# LNA.net
KiCad netlist of a schematic drawn in Altium Designer
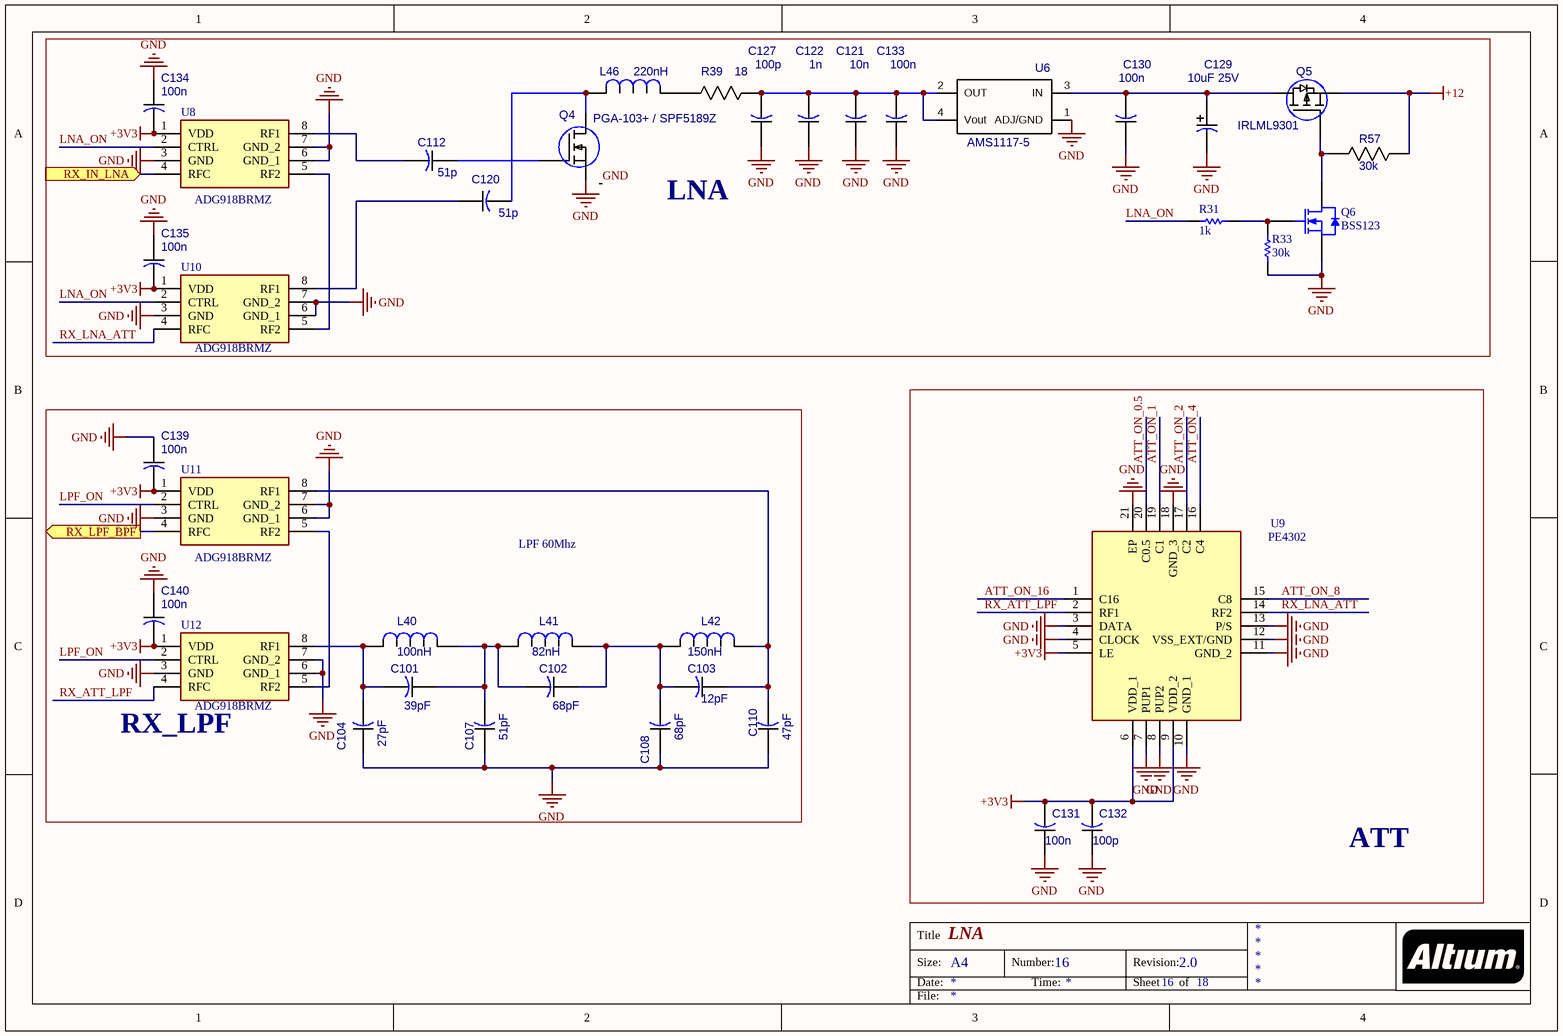
[diagram p0: LNA.SchDoc]

(export (version "E")
  (design (tool "Eeschema 10.0.6"))
  (components
    (comp (ref "C101")
      (value "39pF")
      (footprint "CAP_0805")
      (description "CAP_0805")
      (libsource (lib "*") (part "CAP_0805"))
    )
    (comp (ref "C102")
      (value "68pF")
      (footprint "CAP_0805")
      (description "CAP_0805")
      (libsource (lib "*") (part "CAP_0805"))
    )
    (comp (ref "C103")
      (value "12pF")
      (footprint "CAP_0805")
      (description "CAP_0805")
      (libsource (lib "*") (part "CAP_0805"))
    )
    (comp (ref "C104")
      (value "27pF")
      (footprint "CAP_0805")
      (description "CAP_0805")
      (libsource (lib "*") (part "CAP_0805"))
    )
    (comp (ref "C107")
      (value "51pF")
      (footprint "CAP_0805")
      (description "CAP_0805")
      (libsource (lib "*") (part "CAP_0805"))
    )
    (comp (ref "C108")
      (value "68pF")
      (footprint "CAP_0805")
      (description "CAP_0805")
      (libsource (lib "*") (part "CAP_0805"))
    )
    (comp (ref "C110")
      (value "47pF")
      (footprint "CAP_0805")
      (description "CAP_0805")
      (libsource (lib "*") (part "CAP_0805"))
    )
    (comp (ref "C112")
      (value "51p")
      (footprint "CAP_0805")
      (description "CAP_0805")
      (libsource (lib "*") (part "CAP_0805"))
    )
    (comp (ref "C120")
      (value "51p")
      (footprint "CAP_0805")
      (description "CAP_0805")
      (libsource (lib "*") (part "CAP_0805"))
    )
    (comp (ref "C121")
      (value "10n")
      (footprint "6-0805_M")
      (description "CAP_0805")
      (libsource (lib "*") (part "CAP_0805"))
    )
    (comp (ref "C122")
      (value "1n")
      (footprint "6-0805_M")
      (description "CAP_0805")
      (libsource (lib "*") (part "CAP_0805"))
    )
    (comp (ref "C127")
      (value "100p")
      (footprint "6-0805_M")
      (description "CAP_0805")
      (libsource (lib "*") (part "CAP_0805"))
    )
    (comp (ref "C129")
      (value "10uF 25V")
      (footprint "CAPAE_5.3x5.3h6.1")
      (description "CAPAE_5.3x5.3h6.1")
      (libsource (lib "*") (part "CAPAE_5.3x5.3h6.1"))
    )
    (comp (ref "C130")
      (value "100n")
      (footprint "CAP_0805")
      (description "CAP_0805")
      (libsource (lib "") (part "CAP_0805_1"))
    )
    (comp (ref "C131")
      (value "100n")
      (footprint "6-0805_M")
      (description "CAP_0805")
      (libsource (lib "*") (part "CAP_0805"))
    )
    (comp (ref "C132")
      (value "100p")
      (footprint "6-0805_M")
      (description "CAP_0805")
      (libsource (lib "*") (part "CAP_0805"))
    )
    (comp (ref "C133")
      (value "100n")
      (footprint "CAP_0805")
      (description "CAP_0805")
      (libsource (lib "*") (part "CAP_0805"))
    )
    (comp (ref "C134")
      (value "100n")
      (footprint "CAP_0805")
      (description "CAP_0805")
      (libsource (lib "*") (part "CAP_0805"))
    )
    (comp (ref "C135")
      (value "100n")
      (footprint "CAP_0805")
      (description "CAP_0805")
      (libsource (lib "*") (part "CAP_0805"))
    )
    (comp (ref "C139")
      (value "100n")
      (footprint "CAP_0805")
      (description "CAP_0805")
      (libsource (lib "*") (part "CAP_0805"))
    )
    (comp (ref "C140")
      (value "100n")
      (footprint "CAP_0805")
      (description "CAP_0805")
      (libsource (lib "*") (part "CAP_0805"))
    )
    (comp (ref "L40")
      (value "100nH")
      (footprint "IND_0805")
      (description "IND_0805")
      (libsource (lib "*") (part "IND_0805"))
    )
    (comp (ref "L41")
      (value "82nH")
      (footprint "IND_0805")
      (description "IND_0805")
      (libsource (lib "*") (part "IND_0805"))
    )
    (comp (ref "L42")
      (value "150nH")
      (footprint "IND_0805")
      (description "IND_0805")
      (libsource (lib "*") (part "IND_0805"))
    )
    (comp (ref "L46")
      (value "220nH")
      (footprint "IND_1206")
      (description "IND_1206")
      (libsource (lib "*") (part "IND_1206"))
    )
    (comp (ref "Q4")
      (value "PGA-103+ / SPF5189Z")
      (footprint "SOT89")
      (libsource (lib "*") (part "PGA-103+"))
    )
    (comp (ref "Q5")
      (value "IRLML9301")
      (footprint "SOT23")
      (description "MOSFET")
      (libsource (lib "*") (part "MOSFET_ENH_PD"))
    )
    (comp (ref "Q6")
      (value "BSS123")
      (footprint "FAIR-SOT23-3_V")
      (fields (field (name "MANUFACTURER") "Fairchild"))
      (libsource (lib "Altium Content Vault") (part "NEMOS-GSD-3"))
    )
    (comp (ref "R31")
      (value "1k")
      (footprint "RESC2013X60X40NL20T25")
      (description "RES_0805")
      (fields (field (name "MANUFACTURER") "Panasonic") (field (name "PART NUMBER") "ERA-6AEB303V"))
      (libsource (lib "Altium Content Vault") (part "RES"))
    )
    (comp (ref "R33")
      (value "30k")
      (footprint "RESC2013X60X40NL20T25")
      (description "RES_0805")
      (fields (field (name "MANUFACTURER") "Panasonic") (field (name "PART NUMBER") "ERA-6AEB303V"))
      (libsource (lib "Altium Content Vault") (part "RES"))
    )
    (comp (ref "R39")
      (value "18")
      (footprint "RES_1206")
      (description "RES_1206")
      (libsource (lib "*") (part "RES_1206"))
    )
    (comp (ref "R57")
      (value "30k")
      (footprint "RES_0805")
      (description "RES_0805")
      (libsource (lib "*") (part "RES_0805"))
    )
    (comp (ref "U6") (value "AMS1117-5") (footprint "AMS1117-5") (libsource (lib "*") (part "AMS1117-5")))
    (comp (ref "U8")
      (value "ADG918BRMZ")
      (footprint "SamacSys:SOP65P490X110-8N")
      (description "Integrated Circuit")
      (fields (field (name "MOUSER PART NUMBER") "584-ADG918BRMZ") (field (name "RS PART NUMBER") "4969212P"))
      (libsource (lib "*") (part "ADG918BRMZ"))
    )
    (comp (ref "U9")
      (value "PE4302")
      (footprint "SamacSys:QFN50P400X400X90-21N")
      (description "Integrated Circuit")
      (fields (field (name "MANUFACTURER_PART_NUMBER") "PE4312C-Z"))
      (libsource (lib "*") (part "PE4312C-Z"))
    )
    (comp (ref "U10")
      (value "ADG918BRMZ")
      (footprint "SamacSys:SOP65P490X110-8N")
      (description "Integrated Circuit")
      (fields (field (name "MOUSER PART NUMBER") "584-ADG918BRMZ") (field (name "RS PART NUMBER") "4969212P"))
      (libsource (lib "*") (part "ADG918BRMZ"))
    )
    (comp (ref "U11")
      (value "ADG918BRMZ")
      (footprint "SamacSys:SOP65P490X110-8N")
      (description "Integrated Circuit")
      (fields (field (name "MOUSER PART NUMBER") "584-ADG918BRMZ") (field (name "RS PART NUMBER") "4969212P"))
      (libsource (lib "*") (part "ADG918BRMZ"))
    )
    (comp (ref "U12")
      (value "ADG918BRMZ")
      (footprint "SamacSys:SOP65P490X110-8N")
      (description "Integrated Circuit")
      (fields (field (name "MOUSER PART NUMBER") "584-ADG918BRMZ") (field (name "RS PART NUMBER") "4969212P"))
      (libsource (lib "*") (part "ADG918BRMZ"))
    )
  )
  (nets
    (net (code "1") (name "+3V3") (class "Default")
      (node (ref "C131") (pin "2") (pinfunction "2_2") (pintype "passive"))
      (node (ref "C132") (pin "2") (pinfunction "2_2") (pintype "passive"))
      (node (ref "C134") (pin "2") (pinfunction "2_2") (pintype "passive"))
      (node (ref "C135") (pin "2") (pinfunction "2_2") (pintype "passive"))
      (node (ref "C139") (pin "2") (pinfunction "2_2") (pintype "passive"))
      (node (ref "C140") (pin "2") (pinfunction "2_2") (pintype "passive"))
      (node (ref "U10") (pin "1") (pinfunction "VDD_1") (pintype "power_in"))
      (node (ref "U11") (pin "1") (pinfunction "VDD_1") (pintype "power_in"))
      (node (ref "U12") (pin "1") (pinfunction "VDD_1") (pintype "power_in"))
      (node (ref "U8") (pin "1") (pinfunction "VDD_1") (pintype "power_in"))
      (node (ref "U9") (pin "5") (pinfunction "LE_5") (pintype "passive"))
      (node (ref "U9") (pin "6") (pinfunction "VDD_1_6") (pintype "passive"))
      (node (ref "U9") (pin "9") (pinfunction "VDD_2_9") (pintype "passive"))
    )
    (net (code "2") (name "+12") (class "Default")
      (node (ref "Q5") (pin "2") (pinfunction "S_2") (pintype "passive"))
      (node (ref "R57") (pin "2") (pinfunction "2_2") (pintype "passive"))
    )
    (net (code "3") (name "/ATT_ON_0.5") (class "Default")
      (node (ref "U9") (pin "20") (pinfunction "C0.5_20") (pintype "passive"))
    )
    (net (code "4") (name "/ATT_ON_1") (class "Default")
      (node (ref "U9") (pin "19") (pinfunction "C1_19") (pintype "passive"))
    )
    (net (code "5") (name "/ATT_ON_2") (class "Default")
      (node (ref "U9") (pin "17") (pinfunction "C2_17") (pintype "passive"))
    )
    (net (code "6") (name "/ATT_ON_4") (class "Default")
      (node (ref "U9") (pin "16") (pinfunction "C4_16") (pintype "passive"))
    )
    (net (code "7") (name "/ATT_ON_8") (class "Default")
      (node (ref "U9") (pin "15") (pinfunction "C8_15") (pintype "passive"))
    )
    (net (code "8") (name "/ATT_ON_16") (class "Default")
      (node (ref "U9") (pin "1") (pinfunction "C16_1") (pintype "passive"))
    )
    (net (code "9") (name "/LNA_ON") (class "Default")
      (node (ref "R31") (pin "2") (pinfunction "2_2") (pintype "passive"))
      (node (ref "U10") (pin "2") (pinfunction "CTRL_2") (pintype "passive"))
      (node (ref "U8") (pin "2") (pinfunction "CTRL_2") (pintype "passive"))
    )
    (net (code "10") (name "/LPF_ON") (class "Default")
      (node (ref "U11") (pin "2") (pinfunction "CTRL_2") (pintype "passive"))
      (node (ref "U12") (pin "2") (pinfunction "CTRL_2") (pintype "passive"))
    )
    (net (code "11") (name "/RX_ATT_LPF") (class "Default")
      (node (ref "U12") (pin "4") (pinfunction "RFC_4") (pintype "passive"))
      (node (ref "U9") (pin "2") (pinfunction "RF1_2") (pintype "passive"))
    )
    (net (code "12") (name "/RX_IN_LNA") (class "Default")
      (node (ref "U8") (pin "4") (pinfunction "RFC_4") (pintype "passive"))
    )
    (net (code "13") (name "/RX_LNA_ATT") (class "Default")
      (node (ref "U10") (pin "4") (pinfunction "RFC_4") (pintype "passive"))
      (node (ref "U9") (pin "14") (pinfunction "RF2_14") (pintype "passive"))
    )
    (net (code "14") (name "/RX_LPF_BPF") (class "Default")
      (node (ref "U11") (pin "4") (pinfunction "RFC_4") (pintype "passive"))
    )
    (net (code "15") (name "GND") (class "Default")
      (node (ref "C104") (pin "1") (pinfunction "1_1") (pintype "passive"))
      (node (ref "C107") (pin "1") (pinfunction "1_1") (pintype "passive"))
      (node (ref "C108") (pin "1") (pinfunction "1_1") (pintype "passive"))
      (node (ref "C110") (pin "1") (pinfunction "1_1") (pintype "passive"))
      (node (ref "C121") (pin "1") (pinfunction "1_1") (pintype "passive"))
      (node (ref "C122") (pin "1") (pinfunction "1_1") (pintype "passive"))
      (node (ref "C127") (pin "1") (pinfunction "1_1") (pintype "passive"))
      (node (ref "C129") (pin "2") (pinfunction "MINUS_2") (pintype "passive"))
      (node (ref "C130") (pin "1") (pinfunction "1_1") (pintype "passive"))
      (node (ref "C131") (pin "1") (pinfunction "1_1") (pintype "passive"))
      (node (ref "C132") (pin "1") (pinfunction "1_1") (pintype "passive"))
      (node (ref "C133") (pin "1") (pinfunction "1_1") (pintype "passive"))
      (node (ref "C134") (pin "1") (pinfunction "1_1") (pintype "passive"))
      (node (ref "C135") (pin "1") (pinfunction "1_1") (pintype "passive"))
      (node (ref "C139") (pin "1") (pinfunction "1_1") (pintype "passive"))
      (node (ref "C140") (pin "1") (pinfunction "1_1") (pintype "passive"))
      (node (ref "Q4") (pin "0") (pinfunction "0_0") (pintype "passive"))
      (node (ref "Q4") (pin "2") (pinfunction "S_2") (pintype "passive"))
      (node (ref "Q6") (pin "2") (pinfunction "S_2") (pintype "passive"))
      (node (ref "R33") (pin "1") (pinfunction "1_1") (pintype "passive"))
      (node (ref "U10") (pin "3") (pinfunction "GND_3") (pintype "power_in"))
      (node (ref "U10") (pin "6") (pinfunction "GND_1_6") (pintype "power_in"))
      (node (ref "U10") (pin "7") (pinfunction "GND_2_7") (pintype "power_in"))
      (node (ref "U11") (pin "3") (pinfunction "GND_3") (pintype "power_in"))
      (node (ref "U11") (pin "6") (pinfunction "GND_1_6") (pintype "power_in"))
      (node (ref "U11") (pin "7") (pinfunction "GND_2_7") (pintype "power_in"))
      (node (ref "U12") (pin "3") (pinfunction "GND_3") (pintype "power_in"))
      (node (ref "U12") (pin "6") (pinfunction "GND_1_6") (pintype "power_in"))
      (node (ref "U12") (pin "7") (pinfunction "GND_2_7") (pintype "power_in"))
      (node (ref "U6") (pin "1") (pinfunction "ADJ/GND_1") (pintype "passive"))
      (node (ref "U8") (pin "3") (pinfunction "GND_3") (pintype "power_in"))
      (node (ref "U8") (pin "6") (pinfunction "GND_1_6") (pintype "power_in"))
      (node (ref "U8") (pin "7") (pinfunction "GND_2_7") (pintype "power_in"))
      (node (ref "U9") (pin "10") (pinfunction "GND_1_10") (pintype "passive"))
      (node (ref "U9") (pin "11") (pinfunction "GND_2_11") (pintype "passive"))
      (node (ref "U9") (pin "12") (pinfunction "VSS_EXT/GND_12") (pintype "passive"))
      (node (ref "U9") (pin "13") (pinfunction "P/S_13") (pintype "passive"))
      (node (ref "U9") (pin "18") (pinfunction "GND_3_18") (pintype "passive"))
      (node (ref "U9") (pin "21") (pinfunction "EP_21") (pintype "passive"))
      (node (ref "U9") (pin "3") (pinfunction "DATA_3") (pintype "passive"))
      (node (ref "U9") (pin "4") (pinfunction "CLOCK_4") (pintype "passive"))
      (node (ref "U9") (pin "7") (pinfunction "PUP1_7") (pintype "passive"))
      (node (ref "U9") (pin "8") (pinfunction "PUP2_8") (pintype "passive"))
    )
    (net (code "16") (name "Net-(C101-Pad1)") (class "Default")
      (node (ref "C101") (pin "1") (pinfunction "1_1") (pintype "passive"))
      (node (ref "C102") (pin "2") (pinfunction "2_2") (pintype "passive"))
      (node (ref "C107") (pin "2") (pinfunction "2_2") (pintype "passive"))
      (node (ref "L40") (pin "2") (pinfunction "2_2") (pintype "passive"))
      (node (ref "L41") (pin "1") (pinfunction "1_1") (pintype "passive"))
    )
    (net (code "17") (name "Net-(C102-Pad1)") (class "Default")
      (node (ref "C102") (pin "1") (pinfunction "1_1") (pintype "passive"))
      (node (ref "C103") (pin "2") (pinfunction "2_2") (pintype "passive"))
      (node (ref "C108") (pin "2") (pinfunction "2_2") (pintype "passive"))
      (node (ref "L41") (pin "2") (pinfunction "2_2") (pintype "passive"))
      (node (ref "L42") (pin "1") (pinfunction "1_1") (pintype "passive"))
    )
    (net (code "18") (name "Net-(C129-PLUS)") (class "Default")
      (node (ref "C129") (pin "1") (pinfunction "PLUS_1") (pintype "passive"))
      (node (ref "C130") (pin "2") (pinfunction "2_2") (pintype "passive"))
      (node (ref "Q5") (pin "3") (pinfunction "D_3") (pintype "passive"))
      (node (ref "U6") (pin "3") (pinfunction "IN_3") (pintype "passive"))
    )
    (net (code "19") (name "Net-(L46-1)") (class "Default")
      (node (ref "C120") (pin "2") (pinfunction "2_2") (pintype "passive"))
      (node (ref "L46") (pin "2") (pinfunction "1_2") (pintype "passive"))
      (node (ref "Q4") (pin "3") (pinfunction "D_3") (pintype "passive"))
    )
    (net (code "20") (name "Net-(L46-2)") (class "Default")
      (node (ref "L46") (pin "1") (pinfunction "2_1") (pintype "passive"))
      (node (ref "R39") (pin "2") (pinfunction "2_2") (pintype "passive"))
    )
    (net (code "21") (name "Net-(Q4-G)") (class "Default")
      (node (ref "C112") (pin "1") (pinfunction "1_1") (pintype "passive"))
      (node (ref "Q4") (pin "1") (pinfunction "G_1") (pintype "passive"))
    )
    (net (code "22") (name "Net-(Q5-G)") (class "Default")
      (node (ref "Q5") (pin "1") (pinfunction "G_1") (pintype "passive"))
      (node (ref "Q6") (pin "3") (pinfunction "D_3") (pintype "passive"))
      (node (ref "R57") (pin "1") (pinfunction "1_1") (pintype "passive"))
    )
    (net (code "23") (name "Net-(Q6-G)") (class "Default")
      (node (ref "Q6") (pin "1") (pinfunction "G_1") (pintype "passive"))
      (node (ref "R31") (pin "1") (pinfunction "1_1") (pintype "passive"))
      (node (ref "R33") (pin "2") (pinfunction "2_2") (pintype "passive"))
    )
    (net (code "24") (name "Net-(U6-OUT)") (class "Default")
      (node (ref "C121") (pin "2") (pinfunction "2_2") (pintype "passive"))
      (node (ref "C122") (pin "2") (pinfunction "2_2") (pintype "passive"))
      (node (ref "C127") (pin "2") (pinfunction "2_2") (pintype "passive"))
      (node (ref "C133") (pin "2") (pinfunction "2_2") (pintype "passive"))
      (node (ref "R39") (pin "1") (pinfunction "1_1") (pintype "passive"))
      (node (ref "U6") (pin "2") (pinfunction "OUT_2") (pintype "passive"))
      (node (ref "U6") (pin "4") (pinfunction "Vout_4") (pintype "passive"))
    )
    (net (code "25") (name "Net-(U8-RF1)") (class "Default")
      (node (ref "C112") (pin "2") (pinfunction "2_2") (pintype "passive"))
      (node (ref "U8") (pin "8") (pinfunction "RF1_8") (pintype "passive"))
    )
    (net (code "26") (name "Net-(U10-RF1)") (class "Default")
      (node (ref "C120") (pin "1") (pinfunction "1_1") (pintype "passive"))
      (node (ref "U10") (pin "8") (pinfunction "RF1_8") (pintype "passive"))
    )
    (net (code "27") (name "Net-(U10-RF2)") (class "Default")
      (node (ref "U10") (pin "5") (pinfunction "RF2_5") (pintype "passive"))
      (node (ref "U8") (pin "5") (pinfunction "RF2_5") (pintype "passive"))
    )
    (net (code "28") (name "Net-(U11-RF1)") (class "Default")
      (node (ref "C103") (pin "1") (pinfunction "1_1") (pintype "passive"))
      (node (ref "C110") (pin "2") (pinfunction "2_2") (pintype "passive"))
      (node (ref "L42") (pin "2") (pinfunction "2_2") (pintype "passive"))
      (node (ref "U11") (pin "8") (pinfunction "RF1_8") (pintype "passive"))
    )
    (net (code "29") (name "Net-(U11-RF2)") (class "Default")
      (node (ref "U11") (pin "5") (pinfunction "RF2_5") (pintype "passive"))
      (node (ref "U12") (pin "5") (pinfunction "RF2_5") (pintype "passive"))
    )
    (net (code "30") (name "Net-(U12-RF1)") (class "Default")
      (node (ref "C101") (pin "2") (pinfunction "2_2") (pintype "passive"))
      (node (ref "C104") (pin "2") (pinfunction "2_2") (pintype "passive"))
      (node (ref "L40") (pin "1") (pinfunction "1_1") (pintype "passive"))
      (node (ref "U12") (pin "8") (pinfunction "RF1_8") (pintype "passive"))
    )
  )
)
